# main.net
KiCad netlist of a schematic drawn in Altium Designer
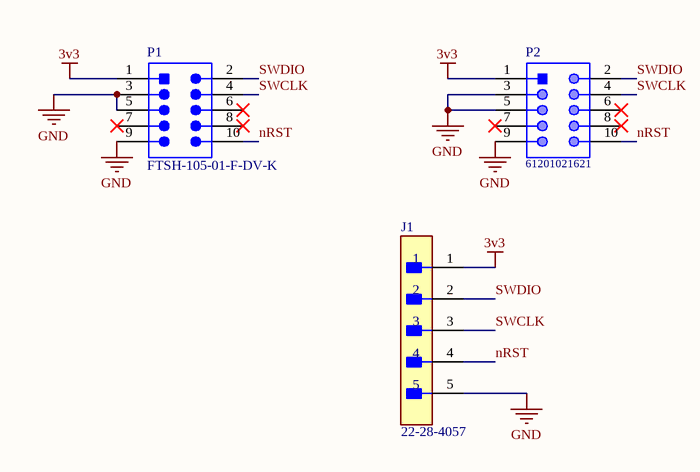
[diagram p0: main.SchDoc]

(export (version "E")
  (design (tool "Eeschema 10.0.6"))
  (components
    (comp (ref "J1")
      (value "22-28-4057")
      (footprint "FP-22-28-4057-MFG")
      (description "KK 100 HDR ASSY BKWY 05 CKT 30 S")
      (libsource (lib "Altium Content Vault") (part "bf93c07fd2649a848d0ec8585582aab"))
    )
    (comp (ref "P1")
      (value "FTSH-105-01-F-DV-K")
      (footprint "SMTC-FTSH-105-01-L-DV-K_V")
      (description "Male Header, Pitch 1.27 mm, 2 x 5 Position, Height 6.12 mm, RoHS, Tube")
      (fields (field (name "MANUFACTURER") "Samtec"))
      (libsource (lib "Altium Content Vault") (part "CN-2P-M-R10"))
    )
    (comp (ref "P2")
      (value "61201021621")
      (footprint "61201021621")
      (description "Male Box Header WR-BHD, THT, Vertical, pitch 2.54 mm, 10 pins")
      (fields (field (name "MANUFACTURER") "Wurth Elektronik") (field (name "PUBLISHER") "WurthElektronik"))
      (libsource (lib "Altium Content Vault") (part "WE-CN-2P-M-R10"))
    )
  )
  (nets
    (net (code "1") (name "/SWCLK") (class "Default")
      (node (ref "J1") (pin "3") (pinfunction "3_3") (pintype "passive"))
      (node (ref "P1") (pin "4") (pinfunction "4_4") (pintype "passive"))
      (node (ref "P2") (pin "4") (pinfunction "4_4") (pintype "passive"))
    )
    (net (code "2") (name "/SWDIO") (class "Default")
      (node (ref "J1") (pin "2") (pinfunction "2_2") (pintype "passive"))
      (node (ref "P1") (pin "2") (pinfunction "2_2") (pintype "passive"))
      (node (ref "P2") (pin "2") (pinfunction "2_2") (pintype "passive"))
    )
    (net (code "3") (name "/nRST") (class "Default")
      (node (ref "J1") (pin "4") (pinfunction "4_4") (pintype "passive"))
      (node (ref "P1") (pin "10") (pinfunction "10_10") (pintype "passive"))
      (node (ref "P2") (pin "10") (pinfunction "10_10") (pintype "passive"))
    )
    (net (code "4") (name "3v3") (class "Default")
      (node (ref "J1") (pin "1") (pinfunction "1_1") (pintype "passive"))
      (node (ref "P1") (pin "1") (pinfunction "1_1") (pintype "passive"))
      (node (ref "P2") (pin "1") (pinfunction "1_1") (pintype "passive"))
    )
    (net (code "5") (name "GND") (class "Default")
      (node (ref "J1") (pin "5") (pinfunction "5_5") (pintype "passive"))
      (node (ref "P1") (pin "3") (pinfunction "3_3") (pintype "passive"))
      (node (ref "P1") (pin "5") (pinfunction "5_5") (pintype "passive"))
      (node (ref "P1") (pin "9") (pinfunction "9_9") (pintype "passive"))
      (node (ref "P2") (pin "3") (pinfunction "3_3") (pintype "passive"))
      (node (ref "P2") (pin "5") (pinfunction "5_5") (pintype "passive"))
      (node (ref "P2") (pin "9") (pinfunction "9_9") (pintype "passive"))
    )
    (net (code "6") (name "unconnected-(P1-Pad6)") (class "Default")
      (node (ref "P1") (pin "6") (pinfunction "6_6") (pintype "passive+no_connect"))
    )
    (net (code "7") (name "unconnected-(P1-Pad7)") (class "Default")
      (node (ref "P1") (pin "7") (pinfunction "7_7") (pintype "passive+no_connect"))
    )
    (net (code "8") (name "unconnected-(P1-Pad8)") (class "Default")
      (node (ref "P1") (pin "8") (pinfunction "8_8") (pintype "passive+no_connect"))
    )
    (net (code "9") (name "unconnected-(P2-Pad6)") (class "Default")
      (node (ref "P2") (pin "6") (pinfunction "6_6") (pintype "passive+no_connect"))
    )
    (net (code "10") (name "unconnected-(P2-Pad7)") (class "Default")
      (node (ref "P2") (pin "7") (pinfunction "7_7") (pintype "passive+no_connect"))
    )
    (net (code "11") (name "unconnected-(P2-Pad8)") (class "Default")
      (node (ref "P2") (pin "8") (pinfunction "8_8") (pintype "passive+no_connect"))
    )
  )
)
